# SensorNodeCat.net
KiCad netlist of a schematic drawn in EAGLE
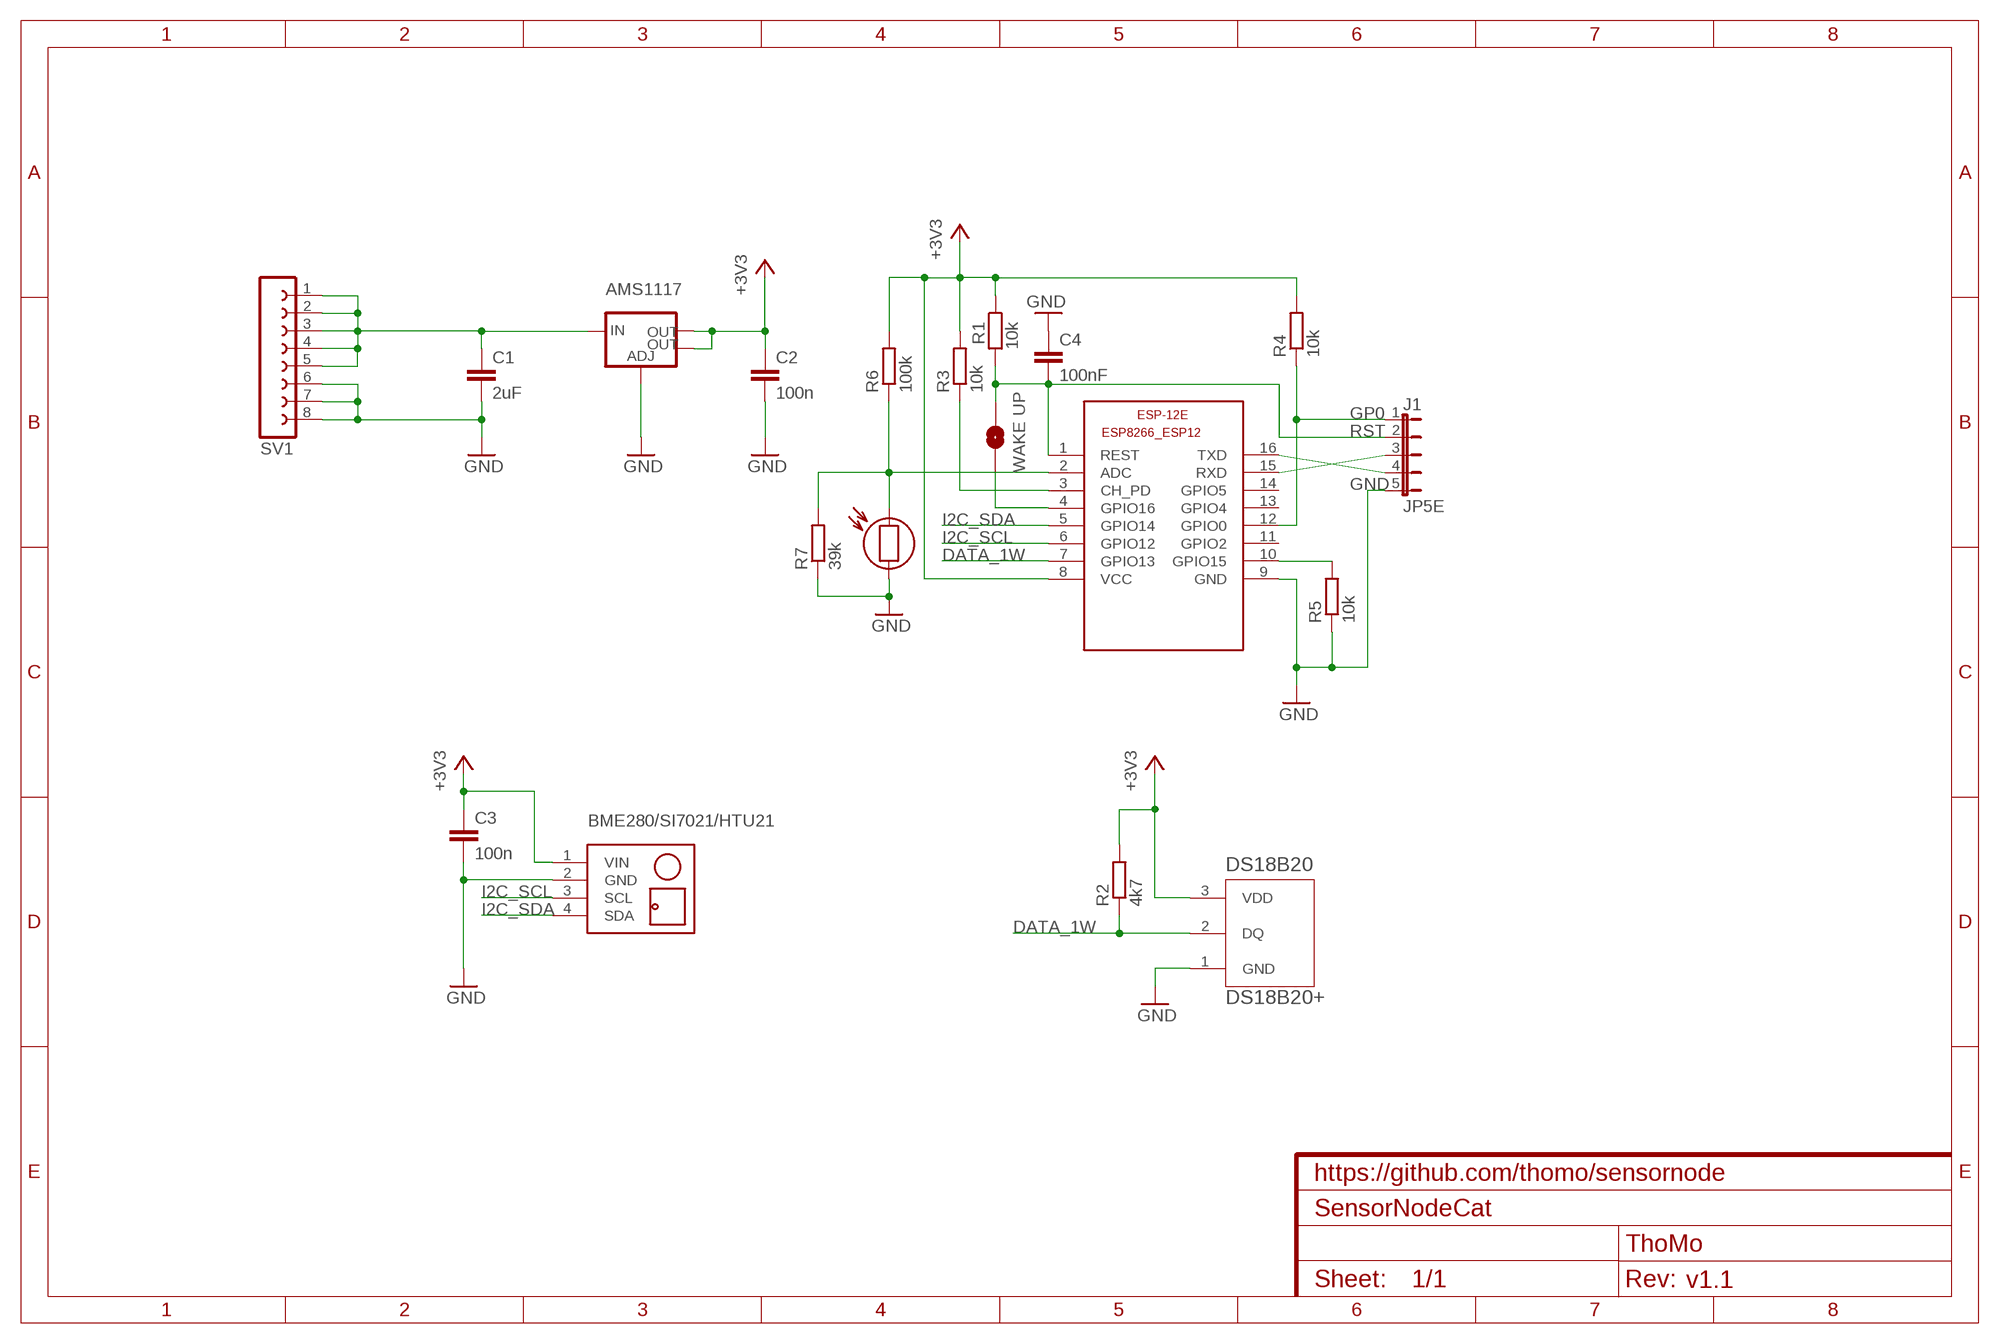
[diagram p0: schematic, sheet 1]

(export (version "E")
  (design (tool "Eeschema 10.0.6"))
  (components
    (comp (ref "AMS1117")
      (value "V_REG_LM1117SOT223")
      (footprint "eagle-import:SOT223")
      (libsource (lib "eagle-import") (part "V_REG_LM1117SOT223"))
    )
    (comp (ref "BME280/SI7021/HTU21")
      (value "BME280")
      (footprint "eagle-import:BME280")
      (libsource (lib "eagle-import") (part "BME280"))
    )
    (comp (ref "C1")
      (value "2uF")
      (footprint "eagle-import:C1206")
      (libsource (lib "eagle-import") (part "C-EUC1206"))
    )
    (comp (ref "C2")
      (value "100n")
      (footprint "eagle-import:C1206")
      (libsource (lib "eagle-import") (part "C-EUC1206"))
    )
    (comp (ref "C3")
      (value "100n")
      (footprint "eagle-import:C1206K")
      (libsource (lib "eagle-import") (part "C-EUC1206K"))
    )
    (comp (ref "C4")
      (value "100nF")
      (footprint "eagle-import:C1206")
      (libsource (lib "eagle-import") (part "C-EUC1206"))
    )
    (comp (ref "DS18B20")
      (value "DS18B20+")
      (footprint "eagle-import:TO-92")
      (libsource (lib "eagle-import") (part "DS18B20+"))
    )
    (comp (ref "ESP-12E")
      (value "ESP8266-12")
      (footprint "eagle-import:ESP8266-ESP12")
      (libsource (lib "eagle-import") (part "ESP8266-12"))
    )
    (comp (ref "J1")
      (value "JP5E")
      (footprint "eagle-import:JP5")
      (libsource (lib "eagle-import") (part "JP5E"))
    )
    (comp (ref "LDR")
      (value "LDR-GL55XX")
      (footprint "eagle-import:GL55")
      (libsource (lib "eagle-import") (part "LDR-GL55XX"))
    )
    (comp (ref "R1")
      (value "10k")
      (footprint "eagle-import:M1206")
      (libsource (lib "eagle-import") (part "R-EU_M1206"))
    )
    (comp (ref "R2")
      (value "4k7")
      (footprint "eagle-import:M1206")
      (libsource (lib "eagle-import") (part "R-EU_M1206"))
    )
    (comp (ref "R3")
      (value "10k")
      (footprint "eagle-import:M1206")
      (libsource (lib "eagle-import") (part "R-EU_M1206"))
    )
    (comp (ref "R4")
      (value "10k")
      (footprint "eagle-import:M1206")
      (libsource (lib "eagle-import") (part "R-EU_M1206"))
    )
    (comp (ref "R5")
      (value "10k")
      (footprint "eagle-import:M1206")
      (libsource (lib "eagle-import") (part "R-EU_M1206"))
    )
    (comp (ref "R6")
      (value "100k")
      (footprint "eagle-import:M1206")
      (libsource (lib "eagle-import") (part "R-EU_M1206"))
    )
    (comp (ref "R7")
      (value "39k")
      (footprint "eagle-import:M1206")
      (libsource (lib "eagle-import") (part "R-EU_M1206"))
    )
    (comp (ref "SV1")
      (value "FE08-1")
      (footprint "eagle-import:FE08")
      (libsource (lib "eagle-import") (part "FE08-1"))
    )
    (comp (ref "WAKEUP")
      (value "WAKE UP")
      (footprint "eagle-import:SMT-JUMPER_2_NO_SILK")
      (libsource (lib "eagle-import") (part "JUMPER-SMT_2_NO_SILK"))
    )
  )
  (nets
    (net (code "1") (name "+3V3") (class "Default")
      (node (ref "AMS1117") (pin "2") (pinfunction "OUT_2") (pintype "output"))
      (node (ref "AMS1117") (pin "4") (pinfunction "OUT_4") (pintype "output"))
      (node (ref "BME280/SI7021/HTU21") (pin "1") (pinfunction "VIN_1") (pintype "power_in"))
      (node (ref "C2") (pin "1") (pinfunction "1_1") (pintype "passive"))
      (node (ref "C3") (pin "1") (pinfunction "1_1") (pintype "passive"))
      (node (ref "DS18B20") (pin "3") (pinfunction "VDD_3") (pintype "power_in"))
      (node (ref "ESP-12E") (pin "8") (pinfunction "VCC_8") (pintype "bidirectional"))
      (node (ref "R1") (pin "1") (pinfunction "1_1") (pintype "passive"))
      (node (ref "R2") (pin "2") (pinfunction "2_2") (pintype "passive"))
      (node (ref "R3") (pin "2") (pinfunction "2_2") (pintype "passive"))
      (node (ref "R4") (pin "2") (pinfunction "2_2") (pintype "passive"))
      (node (ref "R6") (pin "2") (pinfunction "2_2") (pintype "passive"))
    )
    (net (code "2") (name "/DATA_1W") (class "Default")
      (node (ref "DS18B20") (pin "2") (pinfunction "DQ_2") (pintype "bidirectional"))
      (node (ref "ESP-12E") (pin "7") (pinfunction "GPIO13_7") (pintype "bidirectional"))
      (node (ref "R2") (pin "1") (pinfunction "1_1") (pintype "passive"))
    )
    (net (code "3") (name "/GP0") (class "Default")
      (node (ref "ESP-12E") (pin "12") (pinfunction "GPIO0_12") (pintype "bidirectional"))
      (node (ref "J1") (pin "1") (pinfunction "1_1") (pintype "passive"))
      (node (ref "R4") (pin "1") (pinfunction "1_1") (pintype "passive"))
    )
    (net (code "4") (name "/I2C_SCL") (class "Default")
      (node (ref "BME280/SI7021/HTU21") (pin "3") (pinfunction "SCL_3") (pintype "bidirectional"))
      (node (ref "ESP-12E") (pin "6") (pinfunction "GPIO12_6") (pintype "bidirectional"))
    )
    (net (code "5") (name "/I2C_SDA") (class "Default")
      (node (ref "BME280/SI7021/HTU21") (pin "4") (pinfunction "SDA_4") (pintype "bidirectional"))
      (node (ref "ESP-12E") (pin "5") (pinfunction "GPIO14_5") (pintype "bidirectional"))
    )
    (net (code "6") (name "/RST") (class "Default")
      (node (ref "C4") (pin "2") (pinfunction "2_2") (pintype "passive"))
      (node (ref "ESP-12E") (pin "1") (pinfunction "REST_1") (pintype "bidirectional"))
      (node (ref "J1") (pin "2") (pinfunction "2_2") (pintype "passive"))
      (node (ref "R1") (pin "2") (pinfunction "2_2") (pintype "passive"))
      (node (ref "WAKEUP") (pin "2") (pinfunction "2_2") (pintype "passive"))
    )
    (net (code "7") (name "GND") (class "Default")
      (node (ref "AMS1117") (pin "1") (pinfunction "ADJ_1") (pintype "input"))
      (node (ref "BME280/SI7021/HTU21") (pin "2") (pinfunction "GND_2") (pintype "power_in"))
      (node (ref "C1") (pin "2") (pinfunction "2_2") (pintype "passive"))
      (node (ref "C2") (pin "2") (pinfunction "2_2") (pintype "passive"))
      (node (ref "C3") (pin "2") (pinfunction "2_2") (pintype "passive"))
      (node (ref "C4") (pin "1") (pinfunction "1_1") (pintype "passive"))
      (node (ref "DS18B20") (pin "1") (pinfunction "GND_1") (pintype "power_in"))
      (node (ref "ESP-12E") (pin "9") (pinfunction "GND_9") (pintype "bidirectional"))
      (node (ref "J1") (pin "5") (pinfunction "5_5") (pintype "passive"))
      (node (ref "LDR") (pin "2") (pinfunction "2_2") (pintype "passive"))
      (node (ref "R5") (pin "1") (pinfunction "1_1") (pintype "passive"))
      (node (ref "R7") (pin "1") (pinfunction "1_1") (pintype "passive"))
      (node (ref "SV1") (pin "6") (pinfunction "6_6") (pintype "passive"))
      (node (ref "SV1") (pin "7") (pinfunction "7_7") (pintype "passive"))
      (node (ref "SV1") (pin "8") (pinfunction "8_8") (pintype "passive"))
    )
    (net (code "8") (name "Net-(AMS1117-IN)") (class "Default")
      (node (ref "AMS1117") (pin "3") (pinfunction "IN_3") (pintype "input"))
      (node (ref "C1") (pin "1") (pinfunction "1_1") (pintype "passive"))
      (node (ref "SV1") (pin "1") (pinfunction "1_1") (pintype "passive"))
      (node (ref "SV1") (pin "2") (pinfunction "2_2") (pintype "passive"))
      (node (ref "SV1") (pin "3") (pinfunction "3_3") (pintype "passive"))
      (node (ref "SV1") (pin "4") (pinfunction "4_4") (pintype "passive"))
      (node (ref "SV1") (pin "5") (pinfunction "5_5") (pintype "passive"))
    )
    (net (code "9") (name "Net-(ESP-12E-ADC)") (class "Default")
      (node (ref "ESP-12E") (pin "2") (pinfunction "ADC_2") (pintype "bidirectional"))
      (node (ref "LDR") (pin "1") (pinfunction "1_1") (pintype "passive"))
      (node (ref "R6") (pin "1") (pinfunction "1_1") (pintype "passive"))
      (node (ref "R7") (pin "2") (pinfunction "2_2") (pintype "passive"))
    )
    (net (code "10") (name "Net-(ESP-12E-CH_PD)") (class "Default")
      (node (ref "ESP-12E") (pin "3") (pinfunction "CH_PD_3") (pintype "bidirectional"))
      (node (ref "R3") (pin "1") (pinfunction "1_1") (pintype "passive"))
    )
    (net (code "11") (name "Net-(ESP-12E-GPIO15)") (class "Default")
      (node (ref "ESP-12E") (pin "10") (pinfunction "GPIO15_10") (pintype "bidirectional"))
      (node (ref "R5") (pin "2") (pinfunction "2_2") (pintype "passive"))
    )
    (net (code "12") (name "Net-(ESP-12E-GPIO16)") (class "Default")
      (node (ref "ESP-12E") (pin "4") (pinfunction "GPIO16_4") (pintype "bidirectional"))
      (node (ref "WAKEUP") (pin "1") (pinfunction "1_1") (pintype "passive"))
    )
    (net (code "13") (name "Net-(ESP-12E-RXD)") (class "Default")
      (node (ref "ESP-12E") (pin "15") (pinfunction "RXD_15") (pintype "bidirectional"))
      (node (ref "J1") (pin "3") (pinfunction "3_3") (pintype "passive"))
    )
    (net (code "14") (name "Net-(ESP-12E-TXD)") (class "Default")
      (node (ref "ESP-12E") (pin "16") (pinfunction "TXD_16") (pintype "bidirectional"))
      (node (ref "J1") (pin "4") (pinfunction "4_4") (pintype "passive"))
    )
    (net (code "15") (name "unconnected-(ESP-12E-GPIO2-Pad11)") (class "Default")
      (node (ref "ESP-12E") (pin "11") (pinfunction "GPIO2_11") (pintype "bidirectional"))
    )
    (net (code "16") (name "unconnected-(ESP-12E-GPIO4-Pad13)") (class "Default")
      (node (ref "ESP-12E") (pin "13") (pinfunction "GPIO4_13") (pintype "bidirectional"))
    )
    (net (code "17") (name "unconnected-(ESP-12E-GPIO5-Pad14)") (class "Default")
      (node (ref "ESP-12E") (pin "14") (pinfunction "GPIO5_14") (pintype "bidirectional"))
    )
  )
)
